# openSX70_OUTLINE_SONAR_8_20190606B.net
KiCad netlist of a schematic drawn in EAGLE
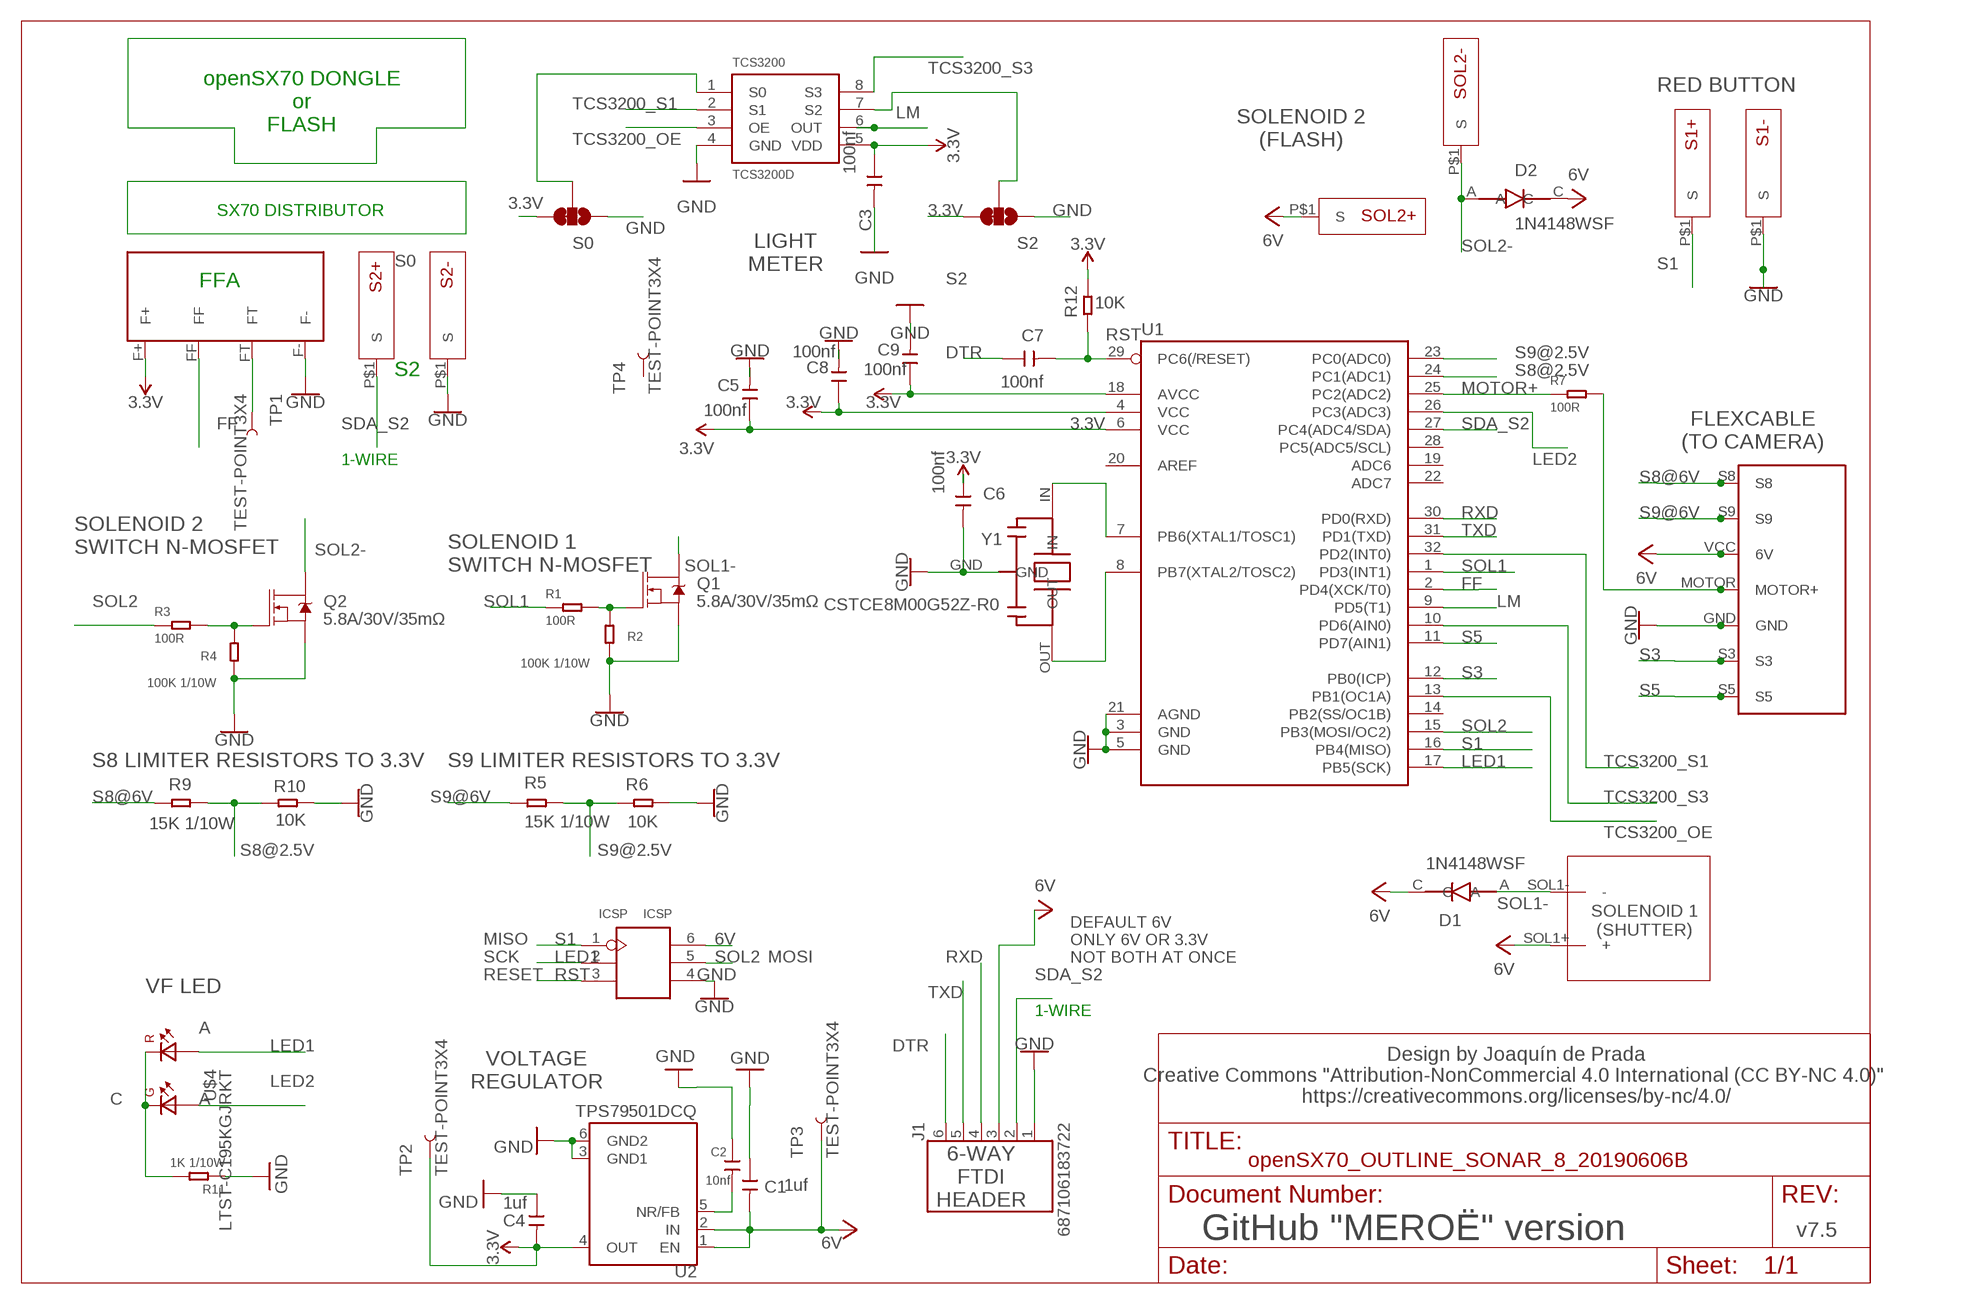
[diagram p0: schematic, sheet 1]

(export (version "E")
  (design (tool "Eeschema 10.0.6"))
  (components
    (comp (ref "C1")
      (value "1uf")
      (footprint "eagle-import:C0603")
      (fields (field (name "MPN") "CC0603KRX5R6BB106"))
      (libsource (lib "eagle-import") (part "CERAMIC-10UF-10V-10%-X5R(0603)"))
    )
    (comp (ref "C2")
      (value "10nf")
      (footprint "eagle-import:C0603")
      (fields (field (name "MPN") "CC0603KRX7R9BB104"))
      (libsource (lib "eagle-import") (part "CERAMIC-100NF-50V-10%-X7R(0603)"))
    )
    (comp (ref "C3")
      (value "100nf")
      (footprint "eagle-import:C0603")
      (fields (field (name "MPN") "CC0603KRX7R9BB104"))
      (libsource (lib "eagle-import") (part "CERAMIC-100NF-50V-10%-X7R(0603)"))
    )
    (comp (ref "C4")
      (value "1uf")
      (footprint "eagle-import:C0603")
      (fields (field (name "MPN") "CC0603KRX5R6BB106"))
      (libsource (lib "eagle-import") (part "CERAMIC-10UF-10V-10%-X5R(0603)"))
    )
    (comp (ref "C5")
      (value "100nf")
      (footprint "eagle-import:C0603")
      (fields (field (name "MPN") "CC0603KRX7R9BB104"))
      (libsource (lib "eagle-import") (part "CERAMIC-100NF-50V-10%-X7R(0603)"))
    )
    (comp (ref "C6")
      (value "100nf")
      (footprint "eagle-import:C0603")
      (fields (field (name "MPN") "CC0603KRX7R9BB104"))
      (libsource (lib "eagle-import") (part "CERAMIC-100NF-50V-10%-X7R(0603)"))
    )
    (comp (ref "C7")
      (value "100nf")
      (footprint "eagle-import:C0603")
      (fields (field (name "MPN") "CC0603KRX7R9BB104"))
      (libsource (lib "eagle-import") (part "CERAMIC-100NF-50V-10%-X7R(0603)"))
    )
    (comp (ref "C8")
      (value "100nf")
      (footprint "eagle-import:C0603")
      (fields (field (name "MPN") "CC0603KRX7R9BB104"))
      (libsource (lib "eagle-import") (part "CERAMIC-100NF-50V-10%-X7R(0603)"))
    )
    (comp (ref "C9")
      (value "100nf")
      (footprint "eagle-import:C0603")
      (fields (field (name "MPN") "CC0603KRX7R9BB104"))
      (libsource (lib "eagle-import") (part "CERAMIC-100NF-50V-10%-X7R(0603)"))
    )
    (comp (ref "D1")
      (value "1N4148WSF")
      (footprint "eagle-import:SODFL2512X100N")
      (fields (field (name "MANUFACTURER") "Fairchild Semiconductor"))
      (libsource (lib "eagle-import") (part "1N4148WS"))
    )
    (comp (ref "D2")
      (value "1N4148WSF")
      (footprint "eagle-import:SODFL2512X100N")
      (fields (field (name "MANUFACTURER") "Fairchild Semiconductor"))
      (libsource (lib "eagle-import") (part "1N4148WS"))
    )
    (comp (ref "ICSP")
      (value "ICSP")
      (footprint "eagle-import:H2X3-2.54")
      (libsource (lib "eagle-import") (part "ICSP"))
    )
    (comp (ref "J1")
      (value "687106183722")
      (footprint "eagle-import:687106183722")
      (fields (field (name "MF") "Wurth Electronics"))
      (libsource (lib "eagle-import") (part "687106183722"))
    )
    (comp (ref "Q1")
      (value "5.8A/30V/35mΩ")
      (footprint "eagle-import:SOT23-3")
      (libsource (lib "eagle-import") (part "MOSFET-NCH-AO3404A"))
    )
    (comp (ref "Q2")
      (value "5.8A/30V/35mΩ")
      (footprint "eagle-import:SOT23-3")
      (libsource (lib "eagle-import") (part "MOSFET-NCH-AO3404A"))
    )
    (comp (ref "R1")
      (value "100R")
      (footprint "eagle-import:R0603")
      (fields (field (name "MPN") "RC0603JR-07100RL"))
      (libsource (lib "eagle-import") (part "SMD-RES-100R-5%-1/10W(0603)"))
    )
    (comp (ref "R2")
      (value "100K 1/10W")
      (footprint "eagle-import:R0603")
      (fields (field (name "MPN") "RC0603JR-07100KL"))
      (libsource (lib "eagle-import") (part "SMD-RES-100K-5%-1/10W(0603)"))
    )
    (comp (ref "R3")
      (value "100R")
      (footprint "eagle-import:R0603")
      (fields (field (name "MPN") "RC0603JR-07100RL"))
      (libsource (lib "eagle-import") (part "SMD-RES-100R-5%-1/10W(0603)"))
    )
    (comp (ref "R4")
      (value "100K 1/10W")
      (footprint "eagle-import:R0603")
      (fields (field (name "MPN") "RC0603JR-07100KL"))
      (libsource (lib "eagle-import") (part "SMD-RES-100K-5%-1/10W(0603)"))
    )
    (comp (ref "R5")
      (value "15K 1/10W")
      (footprint "eagle-import:R0603")
      (fields (field (name "MPN") "RC0603FR-0715KL"))
      (libsource (lib "eagle-import") (part "SMD-RES-15K-1%-1/10W(0603)"))
    )
    (comp (ref "R6")
      (value "10K")
      (footprint "eagle-import:R0603")
      (fields (field (name "MPN") "RC0603FR-0710KL"))
      (libsource (lib "eagle-import") (part "SMD-RES-10K-1%-1/10W(0603)"))
    )
    (comp (ref "R7")
      (value "100R")
      (footprint "eagle-import:R0603")
      (fields (field (name "MPN") "RC0603JR-07100RL"))
      (libsource (lib "eagle-import") (part "SMD-RES-100R-5%-1/10W(0603)"))
    )
    (comp (ref "R9")
      (value "15K 1/10W")
      (footprint "eagle-import:R0603")
      (fields (field (name "MPN") "RC0603FR-0715KL"))
      (libsource (lib "eagle-import") (part "SMD-RES-15K-1%-1/10W(0603)"))
    )
    (comp (ref "R10")
      (value "10K")
      (footprint "eagle-import:R0603")
      (fields (field (name "MPN") "RC0603FR-0710KL"))
      (libsource (lib "eagle-import") (part "SMD-RES-10K-1%-1/10W(0603)"))
    )
    (comp (ref "R11")
      (value "1K 1/10W")
      (footprint "eagle-import:R0603")
      (fields (field (name "MPN") "RC0603JR-071KL"))
      (libsource (lib "eagle-import") (part "SMD-RES-1K-5%-1/10W(0603)"))
    )
    (comp (ref "R12")
      (value "10K")
      (footprint "eagle-import:R0603")
      (fields (field (name "MPN") "RC0603FR-0710KL"))
      (libsource (lib "eagle-import") (part "SMD-RES-10K-1%-1/10W(0603)"))
    )
    (comp (ref "S0")
      (value "S0")
      (footprint "eagle-import:SMT-JUMPER_3_1-NC_TRACE_SILK")
      (libsource (lib "eagle-import") (part "JUMPER-SMT_3_1-NC_TRACE_SILK"))
    )
    (comp (ref "S1+")
      (value "SX70-S-PAD-NEW")
      (footprint "eagle-import:SX70-S-PAD2")
      (libsource (lib "eagle-import") (part "SX70-S-PAD-NEW"))
    )
    (comp (ref "S1-")
      (value "SX70-S-PAD-NEW")
      (footprint "eagle-import:SX70-S-PAD2")
      (libsource (lib "eagle-import") (part "SX70-S-PAD-NEW"))
    )
    (comp (ref "S2")
      (value "S2")
      (footprint "eagle-import:SMT-JUMPER_3_1-NC_TRACE_SILK")
      (libsource (lib "eagle-import") (part "JUMPER-SMT_3_1-NC_TRACE_SILK"))
    )
    (comp (ref "S2+")
      (value "SX70-S-PAD-NEW")
      (footprint "eagle-import:SX70-S-PAD2")
      (libsource (lib "eagle-import") (part "SX70-S-PAD-NEW"))
    )
    (comp (ref "S2-")
      (value "SX70-S-PAD-NEW")
      (footprint "eagle-import:SX70-S-PAD2")
      (libsource (lib "eagle-import") (part "SX70-S-PAD-NEW"))
    )
    (comp (ref "SOL1")
      (value "SX70-SOLENOID1-2PADS")
      (footprint "eagle-import:SX70-SOLENOID1-2")
      (libsource (lib "eagle-import") (part "SX70-SOLENOID1-2PADS"))
    )
    (comp (ref "SOL2+")
      (value "SX70-S-PAD-NEW")
      (footprint "eagle-import:SX70-S-PAD2")
      (libsource (lib "eagle-import") (part "SX70-S-PAD-NEW"))
    )
    (comp (ref "SOL2-")
      (value "SX70-S-PAD-NEW")
      (footprint "eagle-import:SX70-S-PAD2")
      (libsource (lib "eagle-import") (part "SX70-S-PAD-NEW"))
    )
    (comp (ref "TCS3200")
      (value "TCS3200D")
      (footprint "eagle-import:SOIC8")
      (fields (field (name "MF") "ams") (field (name "MP") "TCS3200D-TR"))
      (libsource (lib "eagle-import") (part "TCS3200D"))
    )
    (comp (ref "TP1")
      (value "TEST-POINT3X4")
      (footprint "eagle-import:PAD.03X.04")
      (libsource (lib "eagle-import") (part "TEST-POINT3X4"))
    )
    (comp (ref "TP2")
      (value "TEST-POINT3X4")
      (footprint "eagle-import:PAD.03X.04")
      (libsource (lib "eagle-import") (part "TEST-POINT3X4"))
    )
    (comp (ref "TP3")
      (value "TEST-POINT3X4")
      (footprint "eagle-import:PAD.03X.04")
      (libsource (lib "eagle-import") (part "TEST-POINT3X4"))
    )
    (comp (ref "TP4")
      (value "TEST-POINT3X4")
      (footprint "eagle-import:PAD.03X.04")
      (libsource (lib "eagle-import") (part "TEST-POINT3X4"))
    )
    (comp (ref "U$1")
      (value "SX70-7-PAD")
      (footprint "eagle-import:SX70-7-PAD-PROPER")
      (libsource (lib "eagle-import") (part "SX70-7-PAD"))
    )
    (comp (ref "U$2")
      (value "FFA")
      (footprint "eagle-import:FFA-PAD-PACKAGE")
      (libsource (lib "eagle-import") (part "SX70-FFA-PAD"))
    )
    (comp (ref "U$4")
      (value "LTST-C195KGJRKT")
      (footprint "eagle-import:LTST-BILED-15X16")
      (fields (field (name "MF") "Lite-On Inc."))
      (libsource (lib "eagle-import") (part "LTST-C195KGJRKT"))
    )
    (comp (ref "U1")
      (value "ATMEGA328P_32MLFATMEGA328-MLF")
      (footprint "eagle-import:MLF32")
      (libsource (lib "eagle-import") (part "ATMEGA328P_32MLFATMEGA328-MLF"))
    )
    (comp (ref "U2")
      (value "TPS79501DCQ")
      (footprint "eagle-import:SOT127P706X180-6N")
      (fields (field (name "MF") "Texas Instruments"))
      (libsource (lib "eagle-import") (part "TPS79501DCQ"))
    )
    (comp (ref "Y1")
      (value "CSTCE8M00G52Z-R0")
      (footprint "eagle-import:CFP95P160X100-3N")
      (fields (field (name "MF") "Murata") (field (name "MP") "CSTCE16M0V53-R0"))
      (libsource (lib "eagle-import") (part "CSTCE16M0V53-R0"))
    )
  )
  (nets
    (net (code "1") (name "/DTR") (class "Default")
      (node (ref "C7") (pin "1") (pinfunction "1_1") (pintype "passive"))
      (node (ref "J1") (pin "6") (pinfunction "1_6") (pintype "passive"))
    )
    (net (code "2") (name "/FF") (class "Default")
      (node (ref "U$2") (pin "FF") (pinfunction "FF_FF") (pintype "bidirectional"))
      (node (ref "U1") (pin "2") (pinfunction "PD4(XCK/T0)_2") (pintype "bidirectional"))
    )
    (net (code "3") (name "/LED1") (class "Default")
      (node (ref "ICSP") (pin "2") (pinfunction "SCK_2") (pintype "bidirectional"))
      (node (ref "U$4") (pin "P$2") (pinfunction "A2_P$2") (pintype "passive"))
      (node (ref "U1") (pin "17") (pinfunction "PB5(SCK)_17") (pintype "bidirectional"))
    )
    (net (code "4") (name "/LED2") (class "Default")
      (node (ref "U$4") (pin "P$1") (pinfunction "A1_P$1") (pintype "passive"))
      (node (ref "U1") (pin "26") (pinfunction "PC3(ADC3)_26") (pintype "bidirectional"))
    )
    (net (code "5") (name "/LM") (class "Default")
      (node (ref "TCS3200") (pin "6") (pinfunction "OUT_6") (pintype "bidirectional"))
      (node (ref "U1") (pin "9") (pinfunction "PD5(T1)_9") (pintype "bidirectional"))
    )
    (net (code "6") (name "/MOTOR+") (class "Default")
      (node (ref "R7") (pin "1") (pinfunction "1_1") (pintype "passive"))
      (node (ref "U1") (pin "25") (pinfunction "PC2(ADC2)_25") (pintype "bidirectional"))
    )
    (net (code "7") (name "/RST") (class "Default")
      (node (ref "C7") (pin "2") (pinfunction "2_2") (pintype "passive"))
      (node (ref "ICSP") (pin "3") (pinfunction "RST_3") (pintype "bidirectional"))
      (node (ref "R12") (pin "1") (pinfunction "1_1") (pintype "passive"))
      (node (ref "U1") (pin "29") (pinfunction "PC6(/RESET)_29") (pintype "bidirectional"))
    )
    (net (code "8") (name "/RXD") (class "Default")
      (node (ref "J1") (pin "4") (pinfunction "3_4") (pintype "passive"))
      (node (ref "U1") (pin "30") (pinfunction "PD0(RXD)_30") (pintype "bidirectional"))
    )
    (net (code "9") (name "/S1") (class "Default")
      (node (ref "ICSP") (pin "1") (pinfunction "MISO_1") (pintype "bidirectional"))
      (node (ref "S1+") (pin "P$1") (pinfunction "S_P$1") (pintype "bidirectional"))
      (node (ref "U1") (pin "16") (pinfunction "PB4(MISO)_16") (pintype "bidirectional"))
    )
    (net (code "10") (name "/S3") (class "Default")
      (node (ref "U$1") (pin "S3") (pinfunction "S3_S3") (pintype "bidirectional"))
      (node (ref "U1") (pin "12") (pinfunction "PB0(ICP)_12") (pintype "bidirectional"))
    )
    (net (code "11") (name "/S5") (class "Default")
      (node (ref "U$1") (pin "S5") (pinfunction "S5_S5") (pintype "bidirectional"))
      (node (ref "U1") (pin "11") (pinfunction "PD7(AIN1)_11") (pintype "bidirectional"))
    )
    (net (code "12") (name "/S8@2.5V") (class "Default")
      (node (ref "R10") (pin "1") (pinfunction "1_1") (pintype "passive"))
      (node (ref "R9") (pin "2") (pinfunction "2_2") (pintype "passive"))
      (node (ref "U1") (pin "24") (pinfunction "PC1(ADC1)_24") (pintype "bidirectional"))
    )
    (net (code "13") (name "/S8@6V") (class "Default")
      (node (ref "R9") (pin "1") (pinfunction "1_1") (pintype "passive"))
      (node (ref "U$1") (pin "S8") (pinfunction "S8_S8") (pintype "bidirectional"))
    )
    (net (code "14") (name "/S9@2.5V") (class "Default")
      (node (ref "R5") (pin "2") (pinfunction "2_2") (pintype "passive"))
      (node (ref "R6") (pin "1") (pinfunction "1_1") (pintype "passive"))
      (node (ref "U1") (pin "23") (pinfunction "PC0(ADC0)_23") (pintype "bidirectional"))
    )
    (net (code "15") (name "/S9@6V") (class "Default")
      (node (ref "R5") (pin "1") (pinfunction "1_1") (pintype "passive"))
      (node (ref "U$1") (pin "S9") (pinfunction "S9_S9") (pintype "bidirectional"))
    )
    (net (code "16") (name "/SDA_S2") (class "Default")
      (node (ref "J1") (pin "2") (pinfunction "5_2") (pintype "passive"))
      (node (ref "S2+") (pin "P$1") (pinfunction "S_P$1") (pintype "bidirectional"))
      (node (ref "U1") (pin "27") (pinfunction "PC4(ADC4/SDA)_27") (pintype "bidirectional"))
    )
    (net (code "17") (name "/SOL1") (class "Default")
      (node (ref "R1") (pin "1") (pinfunction "1_1") (pintype "passive"))
      (node (ref "U1") (pin "1") (pinfunction "PD3(INT1)_1") (pintype "bidirectional"))
    )
    (net (code "18") (name "/SOL1-") (class "Default")
      (node (ref "D1") (pin "A") (pinfunction "A_A") (pintype "passive"))
      (node (ref "Q1") (pin "3") (pinfunction "D_3") (pintype "bidirectional"))
      (node (ref "SOL1") (pin "SOL1-") (pinfunction "-_SOL1-") (pintype "bidirectional"))
    )
    (net (code "19") (name "/SOL2") (class "Default")
      (node (ref "ICSP") (pin "5") (pinfunction "MOSI_5") (pintype "bidirectional"))
      (node (ref "R3") (pin "1") (pinfunction "1_1") (pintype "passive"))
      (node (ref "U1") (pin "15") (pinfunction "PB3(MOSI/OC2)_15") (pintype "bidirectional"))
    )
    (net (code "20") (name "/SOL2-") (class "Default")
      (node (ref "D2") (pin "A") (pinfunction "A_A") (pintype "passive"))
      (node (ref "Q2") (pin "3") (pinfunction "D_3") (pintype "bidirectional"))
      (node (ref "SOL2-") (pin "P$1") (pinfunction "S_P$1") (pintype "bidirectional"))
    )
    (net (code "21") (name "/TCS3200_OE") (class "Default")
      (node (ref "TCS3200") (pin "3") (pinfunction "OE_3") (pintype "bidirectional"))
      (node (ref "U1") (pin "13") (pinfunction "PB1(OC1A)_13") (pintype "bidirectional"))
    )
    (net (code "22") (name "/TCS3200_S1") (class "Default")
      (node (ref "TCS3200") (pin "2") (pinfunction "S1_2") (pintype "bidirectional"))
      (node (ref "U1") (pin "32") (pinfunction "PD2(INT0)_32") (pintype "bidirectional"))
    )
    (net (code "23") (name "/TCS3200_S3") (class "Default")
      (node (ref "TCS3200") (pin "8") (pinfunction "S3_8") (pintype "bidirectional"))
      (node (ref "U1") (pin "10") (pinfunction "PD6(AIN0)_10") (pintype "bidirectional"))
    )
    (net (code "24") (name "/TXD") (class "Default")
      (node (ref "J1") (pin "5") (pinfunction "2_5") (pintype "passive"))
      (node (ref "U1") (pin "31") (pinfunction "PD1(TXD)_31") (pintype "bidirectional"))
    )
    (net (code "25") (name "3.3V") (class "Default")
      (node (ref "C3") (pin "1") (pinfunction "1_1") (pintype "passive"))
      (node (ref "C4") (pin "2") (pinfunction "2_2") (pintype "passive"))
      (node (ref "C5") (pin "1") (pinfunction "1_1") (pintype "passive"))
      (node (ref "C6") (pin "1") (pinfunction "1_1") (pintype "passive"))
      (node (ref "C8") (pin "1") (pinfunction "1_1") (pintype "passive"))
      (node (ref "C9") (pin "1") (pinfunction "1_1") (pintype "passive"))
      (node (ref "R12") (pin "2") (pinfunction "2_2") (pintype "passive"))
      (node (ref "S0") (pin "3") (pinfunction "3_3") (pintype "passive"))
      (node (ref "S2") (pin "3") (pinfunction "3_3") (pintype "passive"))
      (node (ref "TCS3200") (pin "5") (pinfunction "VDD_5") (pintype "bidirectional"))
      (node (ref "TP2") (pin "P$1") (pinfunction "1_P$1") (pintype "bidirectional"))
      (node (ref "U$2") (pin "F+") (pinfunction "F+_F+") (pintype "bidirectional"))
      (node (ref "U1") (pin "18") (pinfunction "AVCC_18") (pintype "bidirectional"))
      (node (ref "U1") (pin "4") (pinfunction "VCC_4") (pintype "bidirectional"))
      (node (ref "U1") (pin "6") (pinfunction "VCC_6") (pintype "bidirectional"))
      (node (ref "U2") (pin "4") (pinfunction "OUT_4") (pintype "output"))
    )
    (net (code "26") (name "6V") (class "Default")
      (node (ref "C1") (pin "2") (pinfunction "2_2") (pintype "passive"))
      (node (ref "D1") (pin "C") (pinfunction "C_C") (pintype "passive"))
      (node (ref "D2") (pin "C") (pinfunction "C_C") (pintype "passive"))
      (node (ref "ICSP") (pin "6") (pinfunction "VCC_6") (pintype "bidirectional"))
      (node (ref "J1") (pin "3") (pinfunction "4_3") (pintype "passive"))
      (node (ref "SOL1") (pin "SOL1+") (pinfunction "+_SOL1+") (pintype "bidirectional"))
      (node (ref "SOL2+") (pin "P$1") (pinfunction "S_P$1") (pintype "bidirectional"))
      (node (ref "TP3") (pin "P$1") (pinfunction "1_P$1") (pintype "bidirectional"))
      (node (ref "U$1") (pin "VCC") (pinfunction "6V_VCC") (pintype "bidirectional"))
      (node (ref "U2") (pin "1") (pinfunction "EN_1") (pintype "input"))
      (node (ref "U2") (pin "2") (pinfunction "IN_2") (pintype "input"))
    )
    (net (code "27") (name "GND") (class "Default")
      (node (ref "C1") (pin "1") (pinfunction "1_1") (pintype "passive"))
      (node (ref "C2") (pin "1") (pinfunction "1_1") (pintype "passive"))
      (node (ref "C3") (pin "2") (pinfunction "2_2") (pintype "passive"))
      (node (ref "C4") (pin "1") (pinfunction "1_1") (pintype "passive"))
      (node (ref "C5") (pin "2") (pinfunction "2_2") (pintype "passive"))
      (node (ref "C6") (pin "2") (pinfunction "2_2") (pintype "passive"))
      (node (ref "C8") (pin "2") (pinfunction "2_2") (pintype "passive"))
      (node (ref "C9") (pin "2") (pinfunction "2_2") (pintype "passive"))
      (node (ref "ICSP") (pin "4") (pinfunction "GND_4") (pintype "bidirectional"))
      (node (ref "J1") (pin "1") (pinfunction "6_1") (pintype "passive"))
      (node (ref "Q1") (pin "2") (pinfunction "S_2") (pintype "bidirectional"))
      (node (ref "Q2") (pin "2") (pinfunction "S_2") (pintype "bidirectional"))
      (node (ref "R10") (pin "2") (pinfunction "2_2") (pintype "passive"))
      (node (ref "R11") (pin "1") (pinfunction "1_1") (pintype "passive"))
      (node (ref "R2") (pin "1") (pinfunction "1_1") (pintype "passive"))
      (node (ref "R4") (pin "1") (pinfunction "1_1") (pintype "passive"))
      (node (ref "R6") (pin "2") (pinfunction "2_2") (pintype "passive"))
      (node (ref "S0") (pin "1") (pinfunction "1_1") (pintype "passive"))
      (node (ref "S1-") (pin "P$1") (pinfunction "S_P$1") (pintype "bidirectional"))
      (node (ref "S2") (pin "1") (pinfunction "1_1") (pintype "passive"))
      (node (ref "S2-") (pin "P$1") (pinfunction "S_P$1") (pintype "bidirectional"))
      (node (ref "TCS3200") (pin "4") (pinfunction "GND_4") (pintype "bidirectional"))
      (node (ref "U$1") (pin "GND") (pinfunction "GND_GND") (pintype "bidirectional"))
      (node (ref "U$2") (pin "F-") (pinfunction "F-_F-") (pintype "bidirectional"))
      (node (ref "U1") (pin "21") (pinfunction "AGND_21") (pintype "bidirectional"))
      (node (ref "U1") (pin "3") (pinfunction "GND_3") (pintype "bidirectional"))
      (node (ref "U1") (pin "5") (pinfunction "GND_5") (pintype "bidirectional"))
      (node (ref "U2") (pin "3") (pinfunction "GND1_3") (pintype "power_in"))
      (node (ref "U2") (pin "6") (pinfunction "GND2_6") (pintype "power_in"))
      (node (ref "Y1") (pin "GND") (pinfunction "GND_GND") (pintype "passive"))
    )
    (net (code "28") (name "Net-(Q1-G)") (class "Default")
      (node (ref "Q1") (pin "1") (pinfunction "G_1") (pintype "bidirectional"))
      (node (ref "R1") (pin "2") (pinfunction "2_2") (pintype "passive"))
      (node (ref "R2") (pin "2") (pinfunction "2_2") (pintype "passive"))
    )
    (net (code "29") (name "Net-(Q2-G)") (class "Default")
      (node (ref "Q2") (pin "1") (pinfunction "G_1") (pintype "bidirectional"))
      (node (ref "R3") (pin "2") (pinfunction "2_2") (pintype "passive"))
      (node (ref "R4") (pin "2") (pinfunction "2_2") (pintype "passive"))
    )
    (net (code "30") (name "Net-(TCS3200-S0)") (class "Default")
      (node (ref "S0") (pin "2") (pinfunction "2_2") (pintype "passive"))
      (node (ref "TCS3200") (pin "1") (pinfunction "S0_1") (pintype "bidirectional"))
    )
    (net (code "31") (name "Net-(TCS3200-S2)") (class "Default")
      (node (ref "S2") (pin "2") (pinfunction "2_2") (pintype "passive"))
      (node (ref "TCS3200") (pin "7") (pinfunction "S2_7") (pintype "bidirectional"))
    )
    (net (code "32") (name "Net-(TP1-1)") (class "Default")
      (node (ref "TP1") (pin "P$1") (pinfunction "1_P$1") (pintype "bidirectional"))
      (node (ref "U$2") (pin "FT") (pinfunction "FT_FT") (pintype "bidirectional"))
    )
    (net (code "33") (name "Net-(U$1-MOTOR+)") (class "Default")
      (node (ref "R7") (pin "2") (pinfunction "2_2") (pintype "passive"))
      (node (ref "U$1") (pin "MOTOR") (pinfunction "MOTOR+_MOTOR") (pintype "bidirectional"))
    )
    (net (code "34") (name "Net-(U$4-K1)") (class "Default")
      (node (ref "R11") (pin "2") (pinfunction "2_2") (pintype "passive"))
      (node (ref "U$4") (pin "P$3") (pinfunction "K1_P$3") (pintype "passive"))
      (node (ref "U$4") (pin "P$4") (pinfunction "K2_P$4") (pintype "passive"))
    )
    (net (code "35") (name "Net-(U1-PB6(XTAL1{slash}TOSC1))") (class "Default")
      (node (ref "U1") (pin "7") (pinfunction "PB6(XTAL1/TOSC1)_7") (pintype "bidirectional"))
      (node (ref "Y1") (pin "IN") (pinfunction "IN_IN") (pintype "input"))
    )
    (net (code "36") (name "Net-(U1-PB7(XTAL2{slash}TOSC2))") (class "Default")
      (node (ref "U1") (pin "8") (pinfunction "PB7(XTAL2/TOSC2)_8") (pintype "bidirectional"))
      (node (ref "Y1") (pin "OUT") (pinfunction "OUT_OUT") (pintype "output"))
    )
    (net (code "37") (name "Net-(U2-NR{slash}FB)") (class "Default")
      (node (ref "C2") (pin "2") (pinfunction "2_2") (pintype "passive"))
      (node (ref "U2") (pin "5") (pinfunction "NR/FB_5") (pintype "input"))
    )
    (net (code "38") (name "unconnected-(TP4-1-PadP$1)") (class "Default")
      (node (ref "TP4") (pin "P$1") (pinfunction "1_P$1") (pintype "bidirectional"))
    )
    (net (code "39") (name "unconnected-(U1-ADC6-Pad19)") (class "Default")
      (node (ref "U1") (pin "19") (pinfunction "ADC6_19") (pintype "bidirectional"))
    )
    (net (code "40") (name "unconnected-(U1-ADC7-Pad22)") (class "Default")
      (node (ref "U1") (pin "22") (pinfunction "ADC7_22") (pintype "bidirectional"))
    )
    (net (code "41") (name "unconnected-(U1-AREF-Pad20)") (class "Default")
      (node (ref "U1") (pin "20") (pinfunction "AREF_20") (pintype "bidirectional"))
    )
    (net (code "42") (name "unconnected-(U1-PB2(SS{slash}OC1B)-Pad14)") (class "Default")
      (node (ref "U1") (pin "14") (pinfunction "PB2(SS/OC1B)_14") (pintype "bidirectional"))
    )
    (net (code "43") (name "unconnected-(U1-PC5(ADC5{slash}SCL)-Pad28)") (class "Default")
      (node (ref "U1") (pin "28") (pinfunction "PC5(ADC5/SCL)_28") (pintype "bidirectional"))
    )
  )
)
